# TI_EVM.net
KiCad netlist of a schematic drawn in Altium Designer
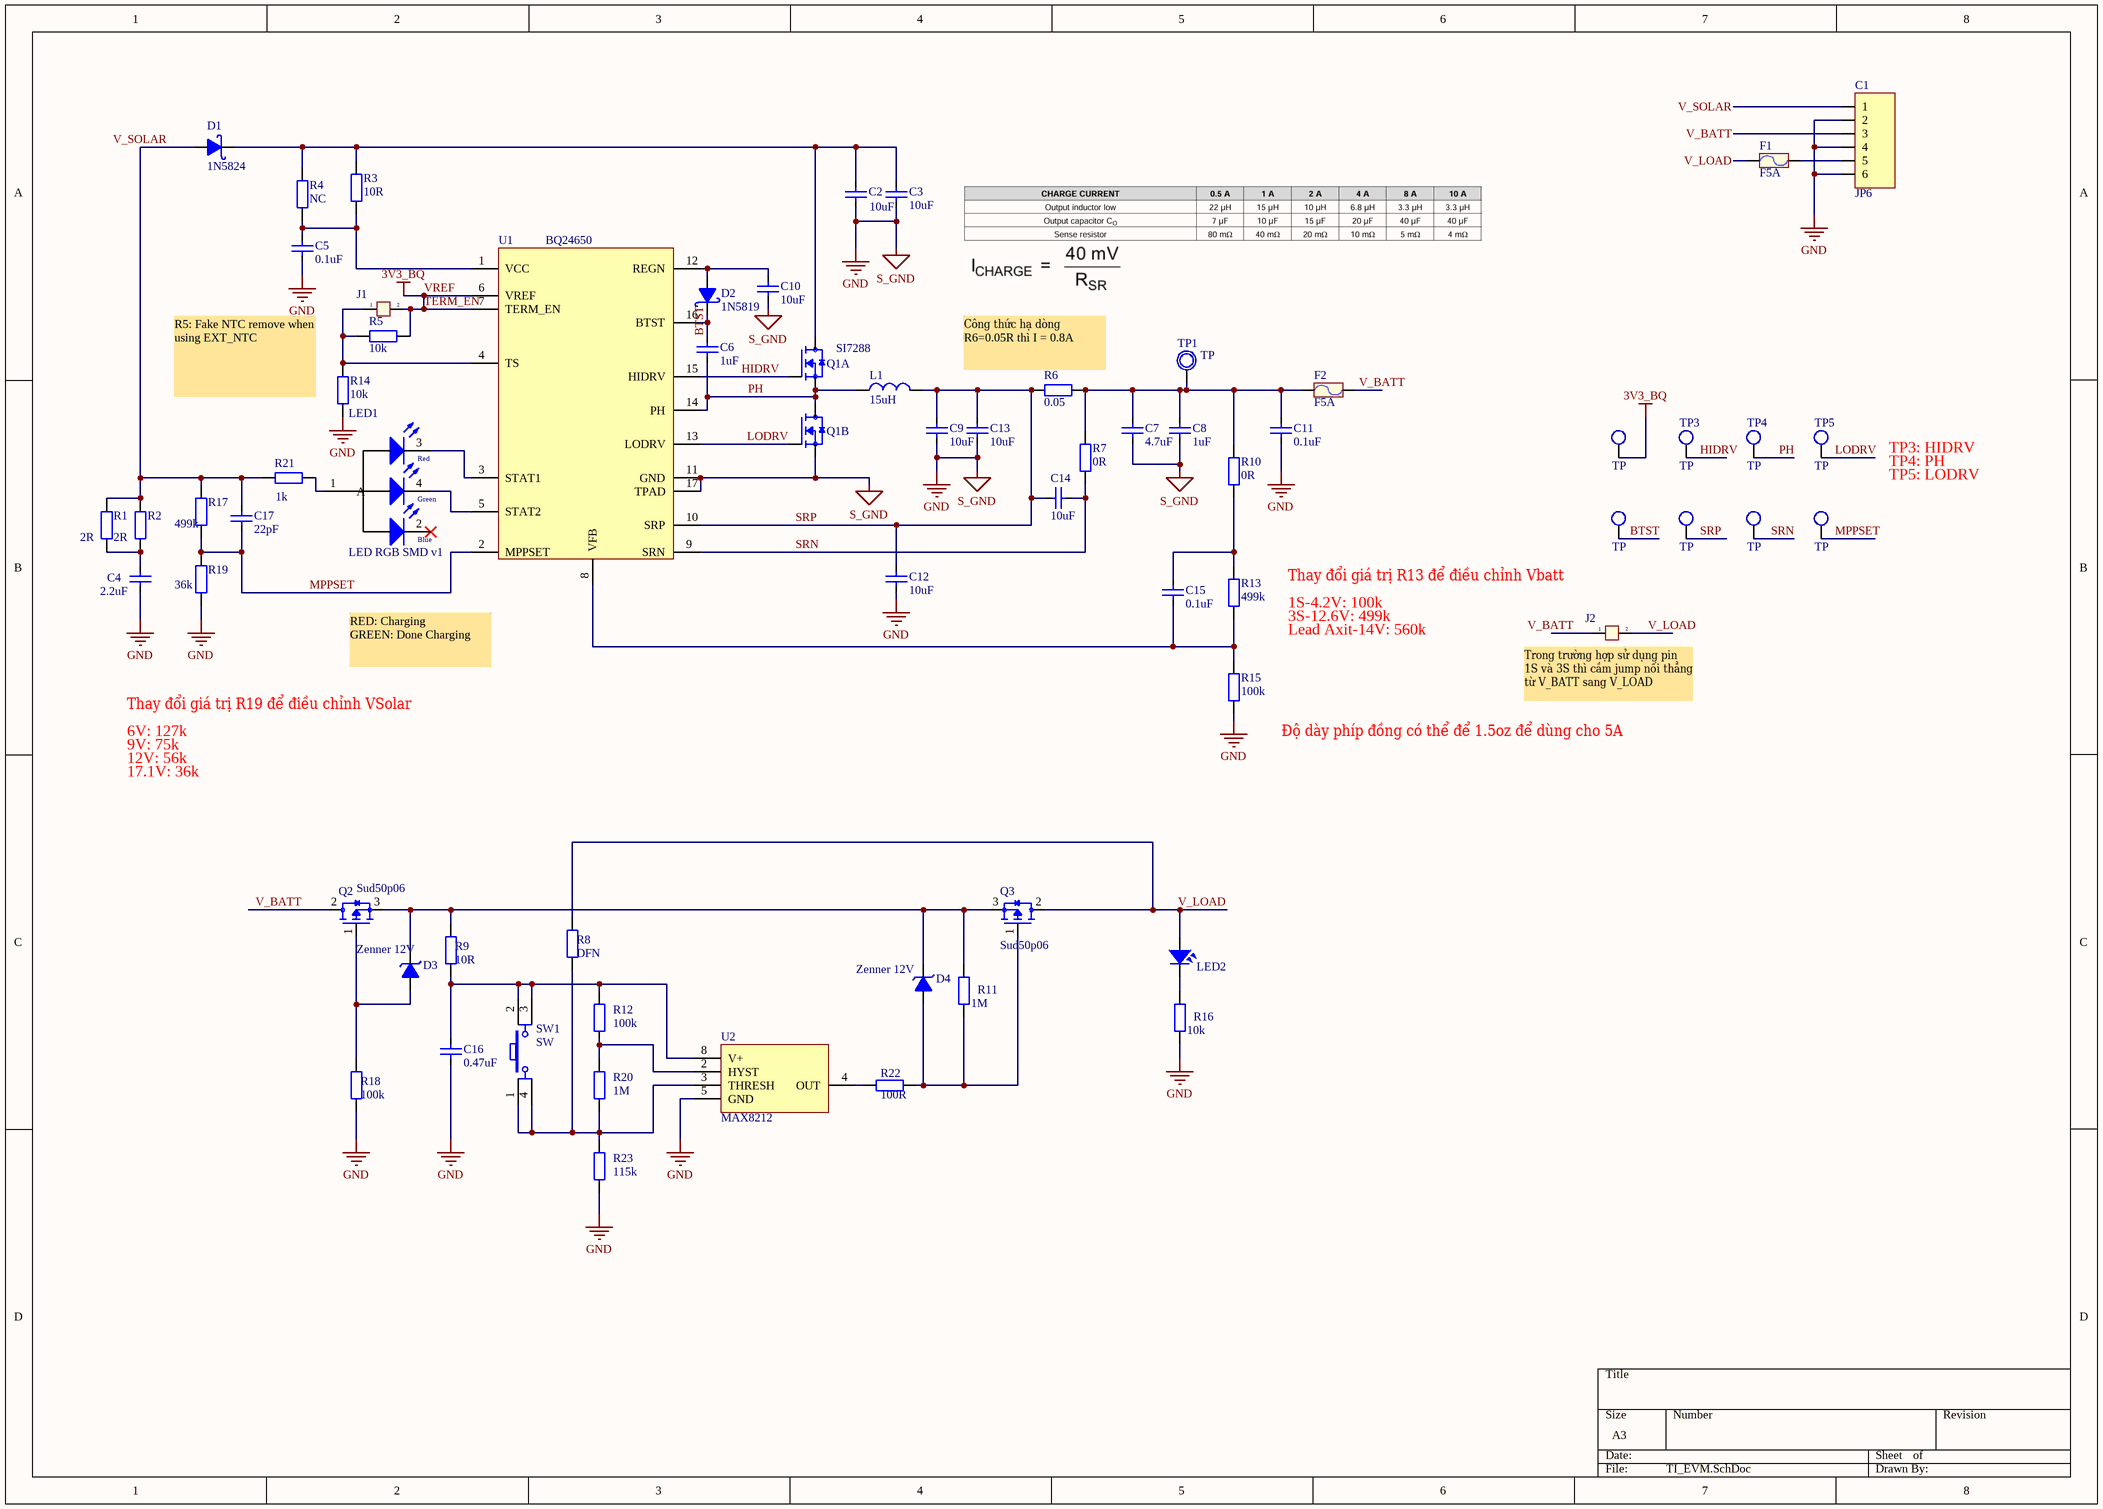
[diagram p0: TI_EVM.SchDoc]

(export (version "E")
  (design (tool "Eeschema 10.0.6"))
  (components
    (comp (ref "C1")
      (value "JP6")
      (footprint "My Library:HB9500-6P")
      (description "WR-PHD 2.54 mm Angled Socket Header")
      (fields
        (field (name "MANUFACTURER") "Würth Elektronik eiSos GmbH")
        (field (name "PARTNO") "613006143121")
        (field (name "CREATED BY") "Karrer Zheng")
      )
      (libsource (lib "Charger+Protection12V_V4") (part "JP6"))
    )
    (comp (ref "C2")
      (value "10uF")
      (footprint "CAP_3216")
      (description "Capacitor")
      (fields (field (name "PUBLISHER") "Altium Limited"))
      (libsource (lib "My Library") (part "CapSMD"))
    )
    (comp (ref "C3")
      (value "10uF")
      (footprint "CAP_3216")
      (description "Capacitor")
      (fields (field (name "PUBLISHER") "Altium Limited"))
      (libsource (lib "My Library") (part "CapSMD"))
    )
    (comp (ref "C4")
      (value "2.2uF")
      (footprint "CAP_0805")
      (description "C_0805")
      (fields (field (name "PUBLISHER") "Altium Limited"))
      (libsource (lib "My Library") (part "CapSMD"))
    )
    (comp (ref "C5")
      (value "0.1uF")
      (footprint "CAP_0805")
      (description "C_0805")
      (fields (field (name "PUBLISHER") "Altium Limited"))
      (libsource (lib "My Library") (part "CapSMD"))
    )
    (comp (ref "C6")
      (value "1uF")
      (footprint "CAP_0805")
      (description "C_0805")
      (fields (field (name "PUBLISHER") "Altium Limited"))
      (libsource (lib "My Library") (part "CapSMD"))
    )
    (comp (ref "C7")
      (value "4.7uF")
      (footprint "CAP_1206")
      (description "C_1206")
      (fields (field (name "PUBLISHER") "Altium Limited"))
      (libsource (lib "My Library") (part "CapSMD"))
    )
    (comp (ref "C8")
      (value "1uF")
      (footprint "CAP_1206")
      (description "C_1206")
      (fields (field (name "PUBLISHER") "Altium Limited"))
      (libsource (lib "My Library") (part "CapSMD"))
    )
    (comp (ref "C9")
      (value "10uF")
      (footprint "CAP_1206")
      (description "C_1206")
      (fields (field (name "PUBLISHER") "Altium Limited"))
      (libsource (lib "My Library") (part "CapSMD"))
    )
    (comp (ref "C10")
      (value "10uF")
      (footprint "CAP_0805")
      (description "C_0805")
      (fields (field (name "PUBLISHER") "Altium Limited"))
      (libsource (lib "My Library") (part "CapSMD"))
    )
    (comp (ref "C11")
      (value "0.1uF")
      (footprint "CAP_0805")
      (description "C_0805")
      (fields (field (name "PUBLISHER") "Altium Limited"))
      (libsource (lib "My Library") (part "CapSMD"))
    )
    (comp (ref "C12")
      (value "10uF")
      (footprint "CAP_0805")
      (description "C_0805")
      (fields (field (name "PUBLISHER") "Altium Limited"))
      (libsource (lib "My Library") (part "CapSMD"))
    )
    (comp (ref "C13")
      (value "10uF")
      (footprint "CAP_1206")
      (description "C_1206")
      (fields (field (name "PUBLISHER") "Altium Limited"))
      (libsource (lib "My Library") (part "CapSMD"))
    )
    (comp (ref "C14")
      (value "10uF")
      (footprint "CAP_0805")
      (description "C_0805")
      (fields (field (name "PUBLISHER") "Altium Limited"))
      (libsource (lib "My Library") (part "CapSMD"))
    )
    (comp (ref "C15")
      (value "0.1uF")
      (footprint "CAP_0805")
      (description "C_0805")
      (fields (field (name "PUBLISHER") "Altium Limited"))
      (libsource (lib "My Library") (part "CapSMD"))
    )
    (comp (ref "C16")
      (value "0.47uF")
      (footprint "CAP_0805")
      (description "C_0805")
      (fields (field (name "PUBLISHER") "Altium Limited"))
      (libsource (lib "My Library") (part "CapSMD"))
    )
    (comp (ref "C17")
      (value "22pF")
      (footprint "CAP_0805")
      (description "C_0805")
      (fields (field (name "PUBLISHER") "Altium Limited"))
      (libsource (lib "My Library") (part "CapSMD"))
    )
    (comp (ref "D1")
      (value "1N5824")
      (footprint "SMA")
      (description "SS54 Diode Schottky 5A 40V")
      (libsource (lib "My Library") (part "1N5822"))
    )
    (comp (ref "D2")
      (value "1N5819")
      (footprint "SMA")
      (description "S4 Diode Schottky 1A 40V")
      (libsource (lib "My Library") (part "1N5822"))
    )
    (comp (ref "D3")
      (value "Zenner 12V")
      (footprint "My Library:DIODE_ZENER_SMD")
      (description "generic zenner diode")
      (libsource (lib "My Library") (part "Zenner"))
    )
    (comp (ref "D4")
      (value "Zenner 12V")
      (footprint "My Library:DIODE_ZENER_SMD")
      (description "generic zenner diode")
      (libsource (lib "My Library") (part "Zenner"))
    )
    (comp (ref "F1")
      (value "F5A")
      (footprint "RES-SMD-1812")
      (description "Fuse 5A")
      (fields (field (name "DESIGNED BY") "VanDungEvn"))
      (libsource (lib "My Library") (part "Fuse"))
    )
    (comp (ref "F2")
      (value "F5A")
      (footprint "RES-SMD-1812")
      (description "Fuse 5A")
      (fields (field (name "DESIGNED BY") "VanDungEvn"))
      (libsource (lib "My Library") (part "Fuse"))
    )
    (comp (ref "J1") (value "Jumper 2") (footprint "JP2") (libsource (lib "My Library") (part "JP 2")))
    (comp (ref "J2") (value "Jumper 2") (footprint "JP2") (libsource (lib "My Library") (part "JP 2")))
    (comp (ref "L1")
      (value "15uH")
      (footprint "L-SMD-M-12x10")
      (description "Inductor")
      (libsource (lib "My Library") (part "Inductor"))
    )
    (comp (ref "LED1")
      (value "LED RGB SMD v1")
      (footprint "Charger+Protection12V_V4:LED RGB 3528")
      (libsource (lib "Charger+Protection12V_V4_2") (part "LED RGB SMD v1"))
    )
    (comp (ref "LED2")
      (value "LED")
      (footprint "LED 3512")
      (libsource (lib "Charger+Protection12V_V4_2") (part "LED SMD"))
    )
    (comp (ref "Q1")
      (value "SI7288")
      (footprint "My Library:SO-8 dual")
      (description "Si7288")
      (libsource (lib "My Library") (part "Dual MOSFET-N"))
    )
    (comp (ref "Q2")
      (value "Sud50p06")
      (footprint "My Library:TO-252")
      (libsource (lib "My Library") (part "MOSFET-P"))
    )
    (comp (ref "Q3")
      (value "Sud50p06")
      (footprint "My Library:TO-252")
      (libsource (lib "My Library") (part "MOSFET-P"))
    )
    (comp (ref "R1")
      (value "2R")
      (footprint "RES-SMD-2512")
      (description "R_2512")
      (fields
        (field (name "MANUFACTURER") "Generic Components")
        (field (name "PUBLISHER") "Altium Hobart Technology Centre")
      )
      (libsource (lib "My Library") (part "Resistor - SMD"))
    )
    (comp (ref "R2")
      (value "2R")
      (footprint "RES-SMD-2512")
      (description "R_2512")
      (fields
        (field (name "MANUFACTURER") "Generic Components")
        (field (name "PUBLISHER") "Altium Hobart Technology Centre")
      )
      (libsource (lib "My Library") (part "Resistor - SMD"))
    )
    (comp (ref "R3")
      (value "10R")
      (footprint "RES-SMD-0805")
      (description "R_0805")
      (fields
        (field (name "MANUFACTURER") "Generic Components")
        (field (name "PUBLISHER") "Altium Hobart Technology Centre")
      )
      (libsource (lib "My Library") (part "Resistor - SMD"))
    )
    (comp (ref "R4")
      (value "NC")
      (footprint "RES-SMD-0805")
      (description "R_0805")
      (fields
        (field (name "MANUFACTURER") "Generic Components")
        (field (name "PUBLISHER") "Altium Hobart Technology Centre")
      )
      (libsource (lib "My Library") (part "Resistor - SMD"))
    )
    (comp (ref "R5")
      (value "10k")
      (footprint "RES-SMD-0805")
      (description "R_0805")
      (fields
        (field (name "MANUFACTURER") "Generic Components")
        (field (name "PUBLISHER") "Altium Hobart Technology Centre")
      )
      (libsource (lib "My Library") (part "Resistor - SMD"))
    )
    (comp (ref "R6")
      (value "0.05")
      (footprint "RES-SMD-2512")
      (description "R_2512")
      (fields
        (field (name "MANUFACTURER") "Generic Components")
        (field (name "PUBLISHER") "Altium Hobart Technology Centre")
      )
      (libsource (lib "My Library") (part "Resistor - SMD"))
    )
    (comp (ref "R7")
      (value "0R")
      (footprint "RES-SMD-0805")
      (description "R_0805")
      (fields
        (field (name "MANUFACTURER") "Generic Components")
        (field (name "PUBLISHER") "Altium Hobart Technology Centre")
      )
      (libsource (lib "My Library") (part "Resistor - SMD"))
    )
    (comp (ref "R8")
      (value "DFN")
      (footprint "RES-SMD-0805")
      (description "R_0805")
      (fields
        (field (name "MANUFACTURER") "Generic Components")
        (field (name "PUBLISHER") "Altium Hobart Technology Centre")
      )
      (libsource (lib "My Library") (part "Resistor - SMD"))
    )
    (comp (ref "R9")
      (value "10R")
      (footprint "RES-SMD-0805")
      (description "R_0805")
      (fields
        (field (name "MANUFACTURER") "Generic Components")
        (field (name "PUBLISHER") "Altium Hobart Technology Centre")
      )
      (libsource (lib "My Library") (part "Resistor - SMD"))
    )
    (comp (ref "R10")
      (value "0R")
      (footprint "RES-SMD-0805")
      (description "R_0805")
      (fields
        (field (name "MANUFACTURER") "Generic Components")
        (field (name "PUBLISHER") "Altium Hobart Technology Centre")
      )
      (libsource (lib "My Library") (part "Resistor - SMD"))
    )
    (comp (ref "R11")
      (value "1M")
      (footprint "RES-SMD-0805")
      (description "R_0805")
      (fields
        (field (name "MANUFACTURER") "Generic Components")
        (field (name "PUBLISHER") "Altium Hobart Technology Centre")
      )
      (libsource (lib "My Library") (part "Resistor - SMD"))
    )
    (comp (ref "R12")
      (value "100k")
      (footprint "RES-SMD-0805")
      (description "R_0805")
      (fields
        (field (name "MANUFACTURER") "Generic Components")
        (field (name "PUBLISHER") "Altium Hobart Technology Centre")
      )
      (libsource (lib "My Library") (part "Resistor - SMD"))
    )
    (comp (ref "R13")
      (value "499k")
      (footprint "RES-SMD-0805")
      (description "R_0805")
      (fields
        (field (name "MANUFACTURER") "Generic Components")
        (field (name "PUBLISHER") "Altium Hobart Technology Centre")
      )
      (libsource (lib "My Library") (part "Resistor - SMD"))
    )
    (comp (ref "R14")
      (value "10k")
      (footprint "RES-SMD-0805")
      (description "R_0805")
      (fields
        (field (name "MANUFACTURER") "Generic Components")
        (field (name "PUBLISHER") "Altium Hobart Technology Centre")
      )
      (libsource (lib "My Library") (part "Resistor - SMD"))
    )
    (comp (ref "R15")
      (value "100k")
      (footprint "RES-SMD-0805")
      (description "R_0805")
      (fields
        (field (name "MANUFACTURER") "Generic Components")
        (field (name "PUBLISHER") "Altium Hobart Technology Centre")
      )
      (libsource (lib "My Library") (part "Resistor - SMD"))
    )
    (comp (ref "R16")
      (value "10k")
      (footprint "RES-SMD-0805")
      (description "R_0805")
      (fields
        (field (name "MANUFACTURER") "Generic Components")
        (field (name "PUBLISHER") "Altium Hobart Technology Centre")
      )
      (libsource (lib "My Library") (part "Resistor - SMD"))
    )
    (comp (ref "R17")
      (value "499k")
      (footprint "RES-SMD-0805")
      (description "R_0805")
      (fields
        (field (name "MANUFACTURER") "Generic Components")
        (field (name "PUBLISHER") "Altium Hobart Technology Centre")
      )
      (libsource (lib "My Library") (part "Resistor - SMD"))
    )
    (comp (ref "R18")
      (value "100k")
      (footprint "RES-SMD-0805")
      (description "R_0805")
      (fields
        (field (name "MANUFACTURER") "Generic Components")
        (field (name "PUBLISHER") "Altium Hobart Technology Centre")
      )
      (libsource (lib "My Library") (part "Resistor - SMD"))
    )
    (comp (ref "R19")
      (value "36k")
      (footprint "RES-SMD-0805")
      (description "R_0805")
      (fields
        (field (name "MANUFACTURER") "Generic Components")
        (field (name "PUBLISHER") "Altium Hobart Technology Centre")
      )
      (libsource (lib "My Library") (part "Resistor - SMD"))
    )
    (comp (ref "R20")
      (value "1M")
      (footprint "RES-SMD-0805")
      (description "R_0805")
      (fields
        (field (name "MANUFACTURER") "Generic Components")
        (field (name "PUBLISHER") "Altium Hobart Technology Centre")
      )
      (libsource (lib "My Library") (part "Resistor - SMD"))
    )
    (comp (ref "R21")
      (value "1k")
      (footprint "RES-SMD-0805")
      (description "R_0805")
      (fields
        (field (name "MANUFACTURER") "Generic Components")
        (field (name "PUBLISHER") "Altium Hobart Technology Centre")
      )
      (libsource (lib "My Library") (part "Resistor - SMD"))
    )
    (comp (ref "R22")
      (value "100R")
      (footprint "RES-SMD-0805")
      (description "R_0805")
      (fields
        (field (name "MANUFACTURER") "Generic Components")
        (field (name "PUBLISHER") "Altium Hobart Technology Centre")
      )
      (libsource (lib "My Library") (part "Resistor - SMD"))
    )
    (comp (ref "R23")
      (value "115k")
      (footprint "RES-SMD-0805")
      (description "R_0805")
      (fields
        (field (name "MANUFACTURER") "Generic Components")
        (field (name "PUBLISHER") "Altium Hobart Technology Centre")
      )
      (libsource (lib "My Library") (part "Resistor - SMD"))
    )
    (comp (ref "SW1")
      (value "SW")
      (footprint "SW4")
      (description "Switch button 4 pin")
      (libsource (lib "My Library") (part "SW4"))
    )
    (comp (ref "TP1")
      (value "TP")
      (footprint "TP1")
      (description "Test Point")
      (libsource (lib "My Library") (part "TP1"))
    )
    (comp (ref "TP2")
      (value "TP")
      (footprint "My Library:Testpoint 50ml")
      (description "Test Point")
      (libsource (lib "My Library") (part "TP_1"))
    )
    (comp (ref "TP3")
      (value "TP")
      (footprint "My Library:Testpoint 50ml")
      (description "Test Point")
      (libsource (lib "My Library") (part "TP_1"))
    )
    (comp (ref "TP4")
      (value "TP")
      (footprint "My Library:Testpoint 50ml")
      (description "Test Point")
      (libsource (lib "My Library") (part "TP_1"))
    )
    (comp (ref "TP5")
      (value "TP")
      (footprint "My Library:Testpoint 50ml")
      (description "Test Point")
      (libsource (lib "My Library") (part "TP_1"))
    )
    (comp (ref "TP6")
      (value "TP")
      (footprint "My Library:Testpoint 50ml")
      (description "Test Point")
      (libsource (lib "My Library") (part "TP_1"))
    )
    (comp (ref "TP7")
      (value "TP")
      (footprint "My Library:Testpoint 50ml")
      (description "Test Point")
      (libsource (lib "My Library") (part "TP_1"))
    )
    (comp (ref "TP8")
      (value "TP")
      (footprint "My Library:Testpoint 50ml")
      (description "Test Point")
      (libsource (lib "My Library") (part "TP_1"))
    )
    (comp (ref "TP9")
      (value "TP")
      (footprint "My Library:Testpoint 50ml")
      (description "Test Point")
      (libsource (lib "My Library") (part "TP_1"))
    )
    (comp (ref "U1") (value "BQ24650") (footprint "VQFN-16") (libsource (lib "My Library") (part "BQ24650")))
    (comp (ref "U2")
      (value "MAX8212")
      (footprint "My Library:SOIC-8")
      (description "Microprocessor Voltage Monitors \r\nwith Programmable Voltage Detection")
      (libsource (lib "My Library") (part "MAX8212"))
    )
  )
  (nets
    (net (code "1") (name "/BTST") (class "Default")
      (node (ref "C6") (pin "2") (pinfunction "2_2") (pintype "passive"))
      (node (ref "D2") (pin "2") (pinfunction "K_2") (pintype "passive"))
      (node (ref "TP6") (pin "1") (pinfunction "1_1") (pintype "passive"))
      (node (ref "U1") (pin "16") (pinfunction "BTST_16") (pintype "passive"))
    )
    (net (code "2") (name "/HIDRV") (class "Default")
      (node (ref "Q1") (pin "2") (pinfunction "G1_2") (pintype "passive"))
      (node (ref "TP3") (pin "1") (pinfunction "1_1") (pintype "passive"))
      (node (ref "U1") (pin "15") (pinfunction "HIDRV_15") (pintype "passive"))
    )
    (net (code "3") (name "/LODRV") (class "Default")
      (node (ref "Q1") (pin "4") (pinfunction "G2_4") (pintype "passive"))
      (node (ref "TP5") (pin "1") (pinfunction "1_1") (pintype "passive"))
      (node (ref "U1") (pin "13") (pinfunction "LODRV_13") (pintype "passive"))
    )
    (net (code "4") (name "/MPPSET") (class "Default")
      (node (ref "C17") (pin "1") (pinfunction "1_1") (pintype "passive"))
      (node (ref "R17") (pin "2") (pinfunction "2_2") (pintype "passive"))
      (node (ref "R19") (pin "1") (pinfunction "1_1") (pintype "passive"))
      (node (ref "TP9") (pin "1") (pinfunction "1_1") (pintype "passive"))
      (node (ref "U1") (pin "2") (pinfunction "MPPSET_2") (pintype "passive"))
    )
    (net (code "5") (name "/PH") (class "Default")
      (node (ref "C6") (pin "1") (pinfunction "1_1") (pintype "passive"))
      (node (ref "L1") (pin "1") (pinfunction "1_1") (pintype "passive"))
      (node (ref "Q1") (pin "1") (pinfunction "S1_1") (pintype "passive"))
      (node (ref "Q1") (pin "5_6_10") (pinfunction "D2_5_6_10") (pintype "passive"))
      (node (ref "TP4") (pin "1") (pinfunction "1_1") (pintype "passive"))
      (node (ref "U1") (pin "14") (pinfunction "PH_14") (pintype "passive"))
    )
    (net (code "6") (name "/SRN") (class "Default")
      (node (ref "C14") (pin "1") (pinfunction "1_1") (pintype "passive"))
      (node (ref "R7") (pin "2") (pinfunction "2_2") (pintype "passive"))
      (node (ref "TP8") (pin "1") (pinfunction "1_1") (pintype "passive"))
      (node (ref "U1") (pin "9") (pinfunction "SRN_9") (pintype "passive"))
    )
    (net (code "7") (name "/SRP") (class "Default")
      (node (ref "C12") (pin "2") (pinfunction "2_2") (pintype "passive"))
      (node (ref "C13") (pin "2") (pinfunction "2_2") (pintype "passive"))
      (node (ref "C14") (pin "2") (pinfunction "2_2") (pintype "passive"))
      (node (ref "C9") (pin "2") (pinfunction "2_2") (pintype "passive"))
      (node (ref "L1") (pin "2") (pinfunction "2_2") (pintype "passive"))
      (node (ref "R6") (pin "2") (pinfunction "2_2") (pintype "passive"))
      (node (ref "TP7") (pin "1") (pinfunction "1_1") (pintype "passive"))
      (node (ref "U1") (pin "10") (pinfunction "SRP_10") (pintype "passive"))
    )
    (net (code "8") (name "/V_BATT") (class "Default")
      (node (ref "C1") (pin "3") (pinfunction "3_3") (pintype "passive"))
      (node (ref "F2") (pin "2") (pinfunction "2_2") (pintype "passive"))
      (node (ref "J2") (pin "1") (pinfunction "1_1") (pintype "passive"))
      (node (ref "Q2") (pin "2") (pinfunction "D_2") (pintype "passive"))
    )
    (net (code "9") (name "/V_LOAD") (class "Default")
      (node (ref "F1") (pin "1") (pinfunction "1_1") (pintype "passive"))
      (node (ref "J2") (pin "2") (pinfunction "2_2") (pintype "passive"))
      (node (ref "LED2") (pin "1") (pinfunction "1_1") (pintype "passive"))
      (node (ref "Q3") (pin "2") (pinfunction "D_2") (pintype "passive"))
      (node (ref "R8") (pin "1") (pinfunction "1_1") (pintype "passive"))
    )
    (net (code "10") (name "/V_SOLAR") (class "Default")
      (node (ref "C1") (pin "1") (pinfunction "1_1") (pintype "passive"))
      (node (ref "C17") (pin "2") (pinfunction "2_2") (pintype "passive"))
      (node (ref "D1") (pin "1") (pinfunction "A_1") (pintype "passive"))
      (node (ref "R1") (pin "1") (pinfunction "1_1") (pintype "passive"))
      (node (ref "R17") (pin "1") (pinfunction "1_1") (pintype "passive"))
      (node (ref "R2") (pin "1") (pinfunction "1_1") (pintype "passive"))
      (node (ref "R21") (pin "2") (pinfunction "2_2") (pintype "passive"))
    )
    (net (code "11") (name "3V3_BQ") (class "Default")
      (node (ref "J1") (pin "2") (pinfunction "2_2") (pintype "passive"))
      (node (ref "R5") (pin "2") (pinfunction "2_2") (pintype "passive"))
      (node (ref "TP2") (pin "1") (pinfunction "1_1") (pintype "passive"))
      (node (ref "U1") (pin "6") (pinfunction "VREF_6") (pintype "passive"))
      (node (ref "U1") (pin "7") (pinfunction "TERM_EN_7") (pintype "passive"))
    )
    (net (code "12") (name "GND") (class "Default")
      (node (ref "C1") (pin "2") (pinfunction "2_2") (pintype "passive"))
      (node (ref "C1") (pin "4") (pinfunction "4_4") (pintype "passive"))
      (node (ref "C1") (pin "6") (pinfunction "6_6") (pintype "passive"))
      (node (ref "C10") (pin "1") (pinfunction "1_1") (pintype "passive"))
      (node (ref "C11") (pin "1") (pinfunction "1_1") (pintype "passive"))
      (node (ref "C12") (pin "1") (pinfunction "1_1") (pintype "passive"))
      (node (ref "C13") (pin "1") (pinfunction "1_1") (pintype "passive"))
      (node (ref "C16") (pin "1") (pinfunction "1_1") (pintype "passive"))
      (node (ref "C2") (pin "1") (pinfunction "1_1") (pintype "passive"))
      (node (ref "C3") (pin "1") (pinfunction "1_1") (pintype "passive"))
      (node (ref "C4") (pin "1") (pinfunction "1_1") (pintype "passive"))
      (node (ref "C5") (pin "1") (pinfunction "1_1") (pintype "passive"))
      (node (ref "C7") (pin "2") (pinfunction "2_2") (pintype "passive"))
      (node (ref "C8") (pin "2") (pinfunction "2_2") (pintype "passive"))
      (node (ref "C9") (pin "1") (pinfunction "1_1") (pintype "passive"))
      (node (ref "Q1") (pin "3") (pinfunction "S2_3") (pintype "passive"))
      (node (ref "R14") (pin "2") (pinfunction "2_2") (pintype "passive"))
      (node (ref "R15") (pin "2") (pinfunction "2_2") (pintype "passive"))
      (node (ref "R16") (pin "2") (pinfunction "2_2") (pintype "passive"))
      (node (ref "R18") (pin "2") (pinfunction "2_2") (pintype "passive"))
      (node (ref "R19") (pin "2") (pinfunction "2_2") (pintype "passive"))
      (node (ref "R23") (pin "2") (pinfunction "2_2") (pintype "passive"))
      (node (ref "U1") (pin "11") (pinfunction "GND_11") (pintype "passive"))
      (node (ref "U1") (pin "17") (pinfunction "TPAD_17") (pintype "passive"))
      (node (ref "U2") (pin "5") (pinfunction "GND_5") (pintype "passive"))
    )
    (net (code "13") (name "Net-(C1-Pad5)") (class "Default")
      (node (ref "C1") (pin "5") (pinfunction "5_5") (pintype "passive"))
      (node (ref "F1") (pin "2") (pinfunction "2_2") (pintype "passive"))
    )
    (net (code "14") (name "Net-(C4-Pad2)") (class "Default")
      (node (ref "C4") (pin "2") (pinfunction "2_2") (pintype "passive"))
      (node (ref "R1") (pin "2") (pinfunction "2_2") (pintype "passive"))
      (node (ref "R2") (pin "2") (pinfunction "2_2") (pintype "passive"))
    )
    (net (code "15") (name "Net-(C11-Pad2)") (class "Default")
      (node (ref "C11") (pin "2") (pinfunction "2_2") (pintype "passive"))
      (node (ref "C7") (pin "1") (pinfunction "1_1") (pintype "passive"))
      (node (ref "C8") (pin "1") (pinfunction "1_1") (pintype "passive"))
      (node (ref "F2") (pin "1") (pinfunction "1_1") (pintype "passive"))
      (node (ref "R10") (pin "1") (pinfunction "1_1") (pintype "passive"))
      (node (ref "R6") (pin "1") (pinfunction "1_1") (pintype "passive"))
      (node (ref "R7") (pin "1") (pinfunction "1_1") (pintype "passive"))
      (node (ref "TP1") (pin "1") (pinfunction "1_1") (pintype "passive"))
    )
    (net (code "16") (name "Net-(C15-Pad2)") (class "Default")
      (node (ref "C15") (pin "2") (pinfunction "2_2") (pintype "passive"))
      (node (ref "R10") (pin "2") (pinfunction "2_2") (pintype "passive"))
      (node (ref "R13") (pin "1") (pinfunction "1_1") (pintype "passive"))
    )
    (net (code "17") (name "Net-(D1-K)") (class "Default")
      (node (ref "C2") (pin "2") (pinfunction "2_2") (pintype "passive"))
      (node (ref "C3") (pin "2") (pinfunction "2_2") (pintype "passive"))
      (node (ref "D1") (pin "2") (pinfunction "K_2") (pintype "passive"))
      (node (ref "Q1") (pin "7_8_9") (pinfunction "D1_7_8_9") (pintype "passive"))
      (node (ref "R3") (pin "1") (pinfunction "1_1") (pintype "passive"))
      (node (ref "R4") (pin "1") (pinfunction "1_1") (pintype "passive"))
    )
    (net (code "18") (name "Net-(D2-A)") (class "Default")
      (node (ref "C10") (pin "2") (pinfunction "2_2") (pintype "passive"))
      (node (ref "D2") (pin "1") (pinfunction "A_1") (pintype "passive"))
      (node (ref "U1") (pin "12") (pinfunction "REGN_12") (pintype "passive"))
    )
    (net (code "19") (name "Net-(D3-A)") (class "Default")
      (node (ref "D3") (pin "1") (pinfunction "A_1") (pintype "passive"))
      (node (ref "Q2") (pin "1") (pinfunction "G_1") (pintype "passive"))
      (node (ref "R18") (pin "1") (pinfunction "1_1") (pintype "passive"))
    )
    (net (code "20") (name "Net-(D3-K)") (class "Default")
      (node (ref "D3") (pin "2") (pinfunction "K_2") (pintype "passive"))
      (node (ref "D4") (pin "2") (pinfunction "K_2") (pintype "passive"))
      (node (ref "Q2") (pin "3") (pinfunction "S_3") (pintype "passive"))
      (node (ref "Q3") (pin "3") (pinfunction "S_3") (pintype "passive"))
      (node (ref "R11") (pin "1") (pinfunction "1_1") (pintype "passive"))
      (node (ref "R9") (pin "1") (pinfunction "1_1") (pintype "passive"))
    )
    (net (code "21") (name "Net-(D4-A)") (class "Default")
      (node (ref "D4") (pin "1") (pinfunction "A_1") (pintype "passive"))
      (node (ref "Q3") (pin "1") (pinfunction "G_1") (pintype "passive"))
      (node (ref "R11") (pin "2") (pinfunction "2_2") (pintype "passive"))
      (node (ref "R22") (pin "2") (pinfunction "2_2") (pintype "passive"))
    )
    (net (code "22") (name "Net-(LED1-A)") (class "Default")
      (node (ref "LED1") (pin "1") (pinfunction "A_1") (pintype "passive"))
      (node (ref "R21") (pin "1") (pinfunction "1_1") (pintype "passive"))
    )
    (net (code "23") (name "Net-(LED1-C1)") (class "Default")
      (node (ref "LED1") (pin "4") (pinfunction "C1_4") (pintype "passive"))
      (node (ref "U1") (pin "5") (pinfunction "STAT2_5") (pintype "passive"))
    )
    (net (code "24") (name "Net-(LED1-C2)") (class "Default")
      (node (ref "LED1") (pin "3") (pinfunction "C2_3") (pintype "passive"))
      (node (ref "U1") (pin "3") (pinfunction "STAT1_3") (pintype "passive"))
    )
    (net (code "25") (name "Net-(LED2-Pad2)") (class "Default")
      (node (ref "LED2") (pin "2") (pinfunction "2_2") (pintype "passive"))
      (node (ref "R16") (pin "1") (pinfunction "1_1") (pintype "passive"))
    )
    (net (code "26") (name "Net-(U1-TS)") (class "Default")
      (node (ref "J1") (pin "1") (pinfunction "1_1") (pintype "passive"))
      (node (ref "R14") (pin "1") (pinfunction "1_1") (pintype "passive"))
      (node (ref "R5") (pin "1") (pinfunction "1_1") (pintype "passive"))
      (node (ref "U1") (pin "4") (pinfunction "TS_4") (pintype "passive"))
    )
    (net (code "27") (name "Net-(U1-VCC)") (class "Default")
      (node (ref "C5") (pin "2") (pinfunction "2_2") (pintype "passive"))
      (node (ref "R3") (pin "2") (pinfunction "2_2") (pintype "passive"))
      (node (ref "R4") (pin "2") (pinfunction "2_2") (pintype "passive"))
      (node (ref "U1") (pin "1") (pinfunction "VCC_1") (pintype "passive"))
    )
    (net (code "28") (name "Net-(U1-VFB)") (class "Default")
      (node (ref "C15") (pin "1") (pinfunction "1_1") (pintype "passive"))
      (node (ref "R13") (pin "2") (pinfunction "2_2") (pintype "passive"))
      (node (ref "R15") (pin "1") (pinfunction "1_1") (pintype "passive"))
      (node (ref "U1") (pin "8") (pinfunction "VFB_8") (pintype "passive"))
    )
    (net (code "29") (name "Net-(U2-HYST)") (class "Default")
      (node (ref "R12") (pin "2") (pinfunction "2_2") (pintype "passive"))
      (node (ref "R20") (pin "1") (pinfunction "1_1") (pintype "passive"))
      (node (ref "U2") (pin "2") (pinfunction "HYST_2") (pintype "passive"))
    )
    (net (code "30") (name "Net-(U2-OUT)") (class "Default")
      (node (ref "R22") (pin "1") (pinfunction "1_1") (pintype "passive"))
      (node (ref "U2") (pin "4") (pinfunction "OUT_4") (pintype "passive"))
    )
    (net (code "31") (name "Net-(U2-THRESH)") (class "Default")
      (node (ref "R20") (pin "2") (pinfunction "2_2") (pintype "passive"))
      (node (ref "R23") (pin "1") (pinfunction "1_1") (pintype "passive"))
      (node (ref "R8") (pin "2") (pinfunction "2_2") (pintype "passive"))
      (node (ref "SW1") (pin "1") (pintype "passive"))
      (node (ref "SW1") (pin "4") (pintype "passive"))
      (node (ref "U2") (pin "3") (pinfunction "THRESH_3") (pintype "passive"))
    )
    (net (code "32") (name "Net-(U2-V+)") (class "Default")
      (node (ref "C16") (pin "2") (pinfunction "2_2") (pintype "passive"))
      (node (ref "R12") (pin "1") (pinfunction "1_1") (pintype "passive"))
      (node (ref "R9") (pin "2") (pinfunction "2_2") (pintype "passive"))
      (node (ref "SW1") (pin "2") (pintype "passive"))
      (node (ref "SW1") (pin "3") (pintype "passive"))
      (node (ref "U2") (pin "8") (pinfunction "V+_8") (pintype "passive"))
    )
    (net (code "33") (name "unconnected-(LED1-C3-Pad2)") (class "Default")
      (node (ref "LED1") (pin "2") (pinfunction "C3_2") (pintype "passive+no_connect"))
    )
  )
)
